# teensyShield1_1.net
KiCad netlist of a schematic drawn in EAGLE
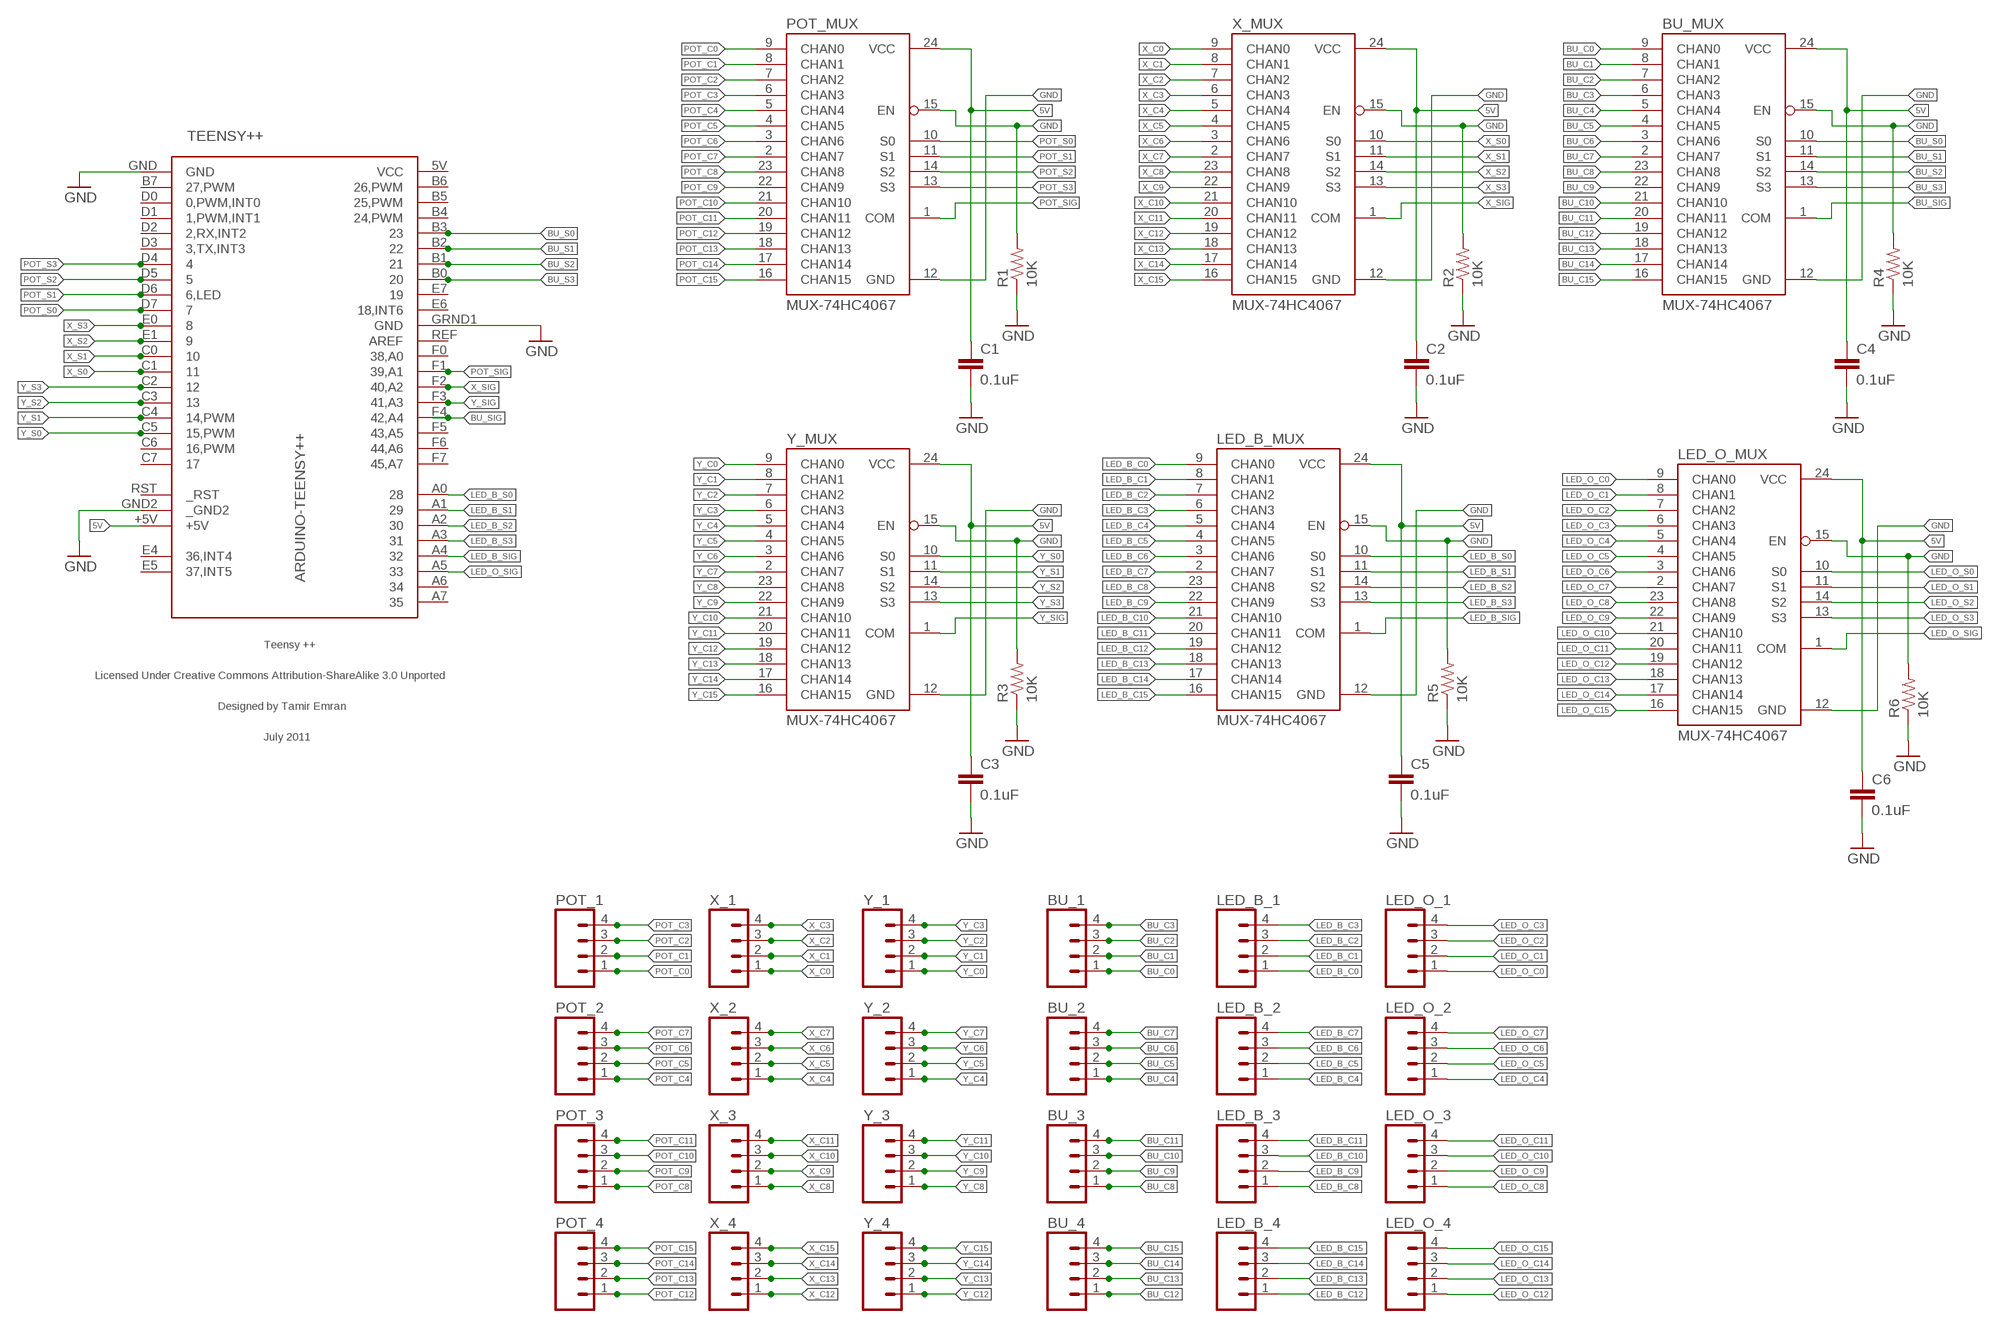
[diagram p0: schematic, sheet 1]

(export (version "E")
  (design (tool "Eeschema 10.0.6"))
  (components
    (comp (ref "BU_1")
      (value "M04NO_SILK_ALL_ROUND")
      (footprint "eagle-import:1X04_NO_SILK_ALL_ROUND")
      (libsource (lib "eagle-import") (part "M04NO_SILK_ALL_ROUND"))
    )
    (comp (ref "BU_2")
      (value "M04NO_SILK_ALL_ROUND")
      (footprint "eagle-import:1X04_NO_SILK_ALL_ROUND")
      (libsource (lib "eagle-import") (part "M04NO_SILK_ALL_ROUND"))
    )
    (comp (ref "BU_3")
      (value "M04NO_SILK_ALL_ROUND")
      (footprint "eagle-import:1X04_NO_SILK_ALL_ROUND")
      (libsource (lib "eagle-import") (part "M04NO_SILK_ALL_ROUND"))
    )
    (comp (ref "BU_4")
      (value "M04NO_SILK_ALL_ROUND")
      (footprint "eagle-import:1X04_NO_SILK_ALL_ROUND")
      (libsource (lib "eagle-import") (part "M04NO_SILK_ALL_ROUND"))
    )
    (comp (ref "BU_MUX")
      (value "MUX-74HC4067")
      (footprint "eagle-import:SSOP24")
      (libsource (lib "eagle-import") (part "MUX-74HC4067SMD"))
    )
    (comp (ref "C1")
      (value "0.1uF")
      (footprint "eagle-import:0603")
      (libsource (lib "eagle-import") (part "CAP0603"))
    )
    (comp (ref "C2")
      (value "0.1uF")
      (footprint "eagle-import:0603")
      (libsource (lib "eagle-import") (part "CAP0603"))
    )
    (comp (ref "C3")
      (value "0.1uF")
      (footprint "eagle-import:0603")
      (libsource (lib "eagle-import") (part "CAP0603"))
    )
    (comp (ref "C4")
      (value "0.1uF")
      (footprint "eagle-import:0603")
      (libsource (lib "eagle-import") (part "CAP0603"))
    )
    (comp (ref "C5")
      (value "0.1uF")
      (footprint "eagle-import:0603")
      (libsource (lib "eagle-import") (part "CAP0603"))
    )
    (comp (ref "C6")
      (value "0.1uF")
      (footprint "eagle-import:0603")
      (libsource (lib "eagle-import") (part "CAP0603"))
    )
    (comp (ref "LED_B_1")
      (value "M04NO_SILK_ALL_ROUND")
      (footprint "eagle-import:1X04_NO_SILK_ALL_ROUND")
      (libsource (lib "eagle-import") (part "M04NO_SILK_ALL_ROUND"))
    )
    (comp (ref "LED_B_2")
      (value "M04NO_SILK_ALL_ROUND")
      (footprint "eagle-import:1X04_NO_SILK_ALL_ROUND")
      (libsource (lib "eagle-import") (part "M04NO_SILK_ALL_ROUND"))
    )
    (comp (ref "LED_B_3")
      (value "M04NO_SILK_ALL_ROUND")
      (footprint "eagle-import:1X04_NO_SILK_ALL_ROUND")
      (libsource (lib "eagle-import") (part "M04NO_SILK_ALL_ROUND"))
    )
    (comp (ref "LED_B_4")
      (value "M04NO_SILK_ALL_ROUND")
      (footprint "eagle-import:1X04_NO_SILK_ALL_ROUND")
      (libsource (lib "eagle-import") (part "M04NO_SILK_ALL_ROUND"))
    )
    (comp (ref "LED_B_MUX")
      (value "MUX-74HC4067")
      (footprint "eagle-import:SSOP24")
      (libsource (lib "eagle-import") (part "MUX-74HC4067SMD"))
    )
    (comp (ref "LED_O_1")
      (value "M04NO_SILK_ALL_ROUND")
      (footprint "eagle-import:1X04_NO_SILK_ALL_ROUND")
      (libsource (lib "eagle-import") (part "M04NO_SILK_ALL_ROUND"))
    )
    (comp (ref "LED_O_2")
      (value "M04NO_SILK_ALL_ROUND")
      (footprint "eagle-import:1X04_NO_SILK_ALL_ROUND")
      (libsource (lib "eagle-import") (part "M04NO_SILK_ALL_ROUND"))
    )
    (comp (ref "LED_O_3")
      (value "M04NO_SILK_ALL_ROUND")
      (footprint "eagle-import:1X04_NO_SILK_ALL_ROUND")
      (libsource (lib "eagle-import") (part "M04NO_SILK_ALL_ROUND"))
    )
    (comp (ref "LED_O_4")
      (value "M04NO_SILK_ALL_ROUND")
      (footprint "eagle-import:1X04_NO_SILK_ALL_ROUND")
      (libsource (lib "eagle-import") (part "M04NO_SILK_ALL_ROUND"))
    )
    (comp (ref "LED_O_MUX")
      (value "MUX-74HC4067")
      (footprint "eagle-import:SSOP24")
      (libsource (lib "eagle-import") (part "MUX-74HC4067SMD"))
    )
    (comp (ref "POT_1")
      (value "M04NO_SILK_ALL_ROUND")
      (footprint "eagle-import:1X04_NO_SILK_ALL_ROUND")
      (libsource (lib "eagle-import") (part "M04NO_SILK_ALL_ROUND"))
    )
    (comp (ref "POT_2")
      (value "M04NO_SILK_ALL_ROUND")
      (footprint "eagle-import:1X04_NO_SILK_ALL_ROUND")
      (libsource (lib "eagle-import") (part "M04NO_SILK_ALL_ROUND"))
    )
    (comp (ref "POT_3")
      (value "M04NO_SILK_ALL_ROUND")
      (footprint "eagle-import:1X04_NO_SILK_ALL_ROUND")
      (libsource (lib "eagle-import") (part "M04NO_SILK_ALL_ROUND"))
    )
    (comp (ref "POT_4")
      (value "M04NO_SILK_ALL_ROUND")
      (footprint "eagle-import:1X04_NO_SILK_ALL_ROUND")
      (libsource (lib "eagle-import") (part "M04NO_SILK_ALL_ROUND"))
    )
    (comp (ref "POT_MUX")
      (value "MUX-74HC4067")
      (footprint "eagle-import:SSOP24")
      (libsource (lib "eagle-import") (part "MUX-74HC4067SMD"))
    )
    (comp (ref "R1")
      (value "10K")
      (footprint "eagle-import:0603")
      (libsource (lib "eagle-import") (part "RESISTOR0603"))
    )
    (comp (ref "R2")
      (value "10K")
      (footprint "eagle-import:0603")
      (libsource (lib "eagle-import") (part "RESISTOR0603"))
    )
    (comp (ref "R3")
      (value "10K")
      (footprint "eagle-import:0603")
      (libsource (lib "eagle-import") (part "RESISTOR0603"))
    )
    (comp (ref "R4")
      (value "10K")
      (footprint "eagle-import:0603")
      (libsource (lib "eagle-import") (part "RESISTOR0603"))
    )
    (comp (ref "R5")
      (value "10K")
      (footprint "eagle-import:0603")
      (libsource (lib "eagle-import") (part "RESISTOR0603"))
    )
    (comp (ref "R6")
      (value "10K")
      (footprint "eagle-import:0603")
      (libsource (lib "eagle-import") (part "RESISTOR0603"))
    )
    (comp (ref "TEENSY++")
      (value "ARDUINO-TEENSY++")
      (footprint "eagle-import:TEENSY++")
      (libsource (lib "eagle-import") (part "ARDUINO-TEENSY++"))
    )
    (comp (ref "X_1")
      (value "M04NO_SILK_ALL_ROUND")
      (footprint "eagle-import:1X04_NO_SILK_ALL_ROUND")
      (libsource (lib "eagle-import") (part "M04NO_SILK_ALL_ROUND"))
    )
    (comp (ref "X_2")
      (value "M04NO_SILK_ALL_ROUND")
      (footprint "eagle-import:1X04_NO_SILK_ALL_ROUND")
      (libsource (lib "eagle-import") (part "M04NO_SILK_ALL_ROUND"))
    )
    (comp (ref "X_3")
      (value "M04NO_SILK_ALL_ROUND")
      (footprint "eagle-import:1X04_NO_SILK_ALL_ROUND")
      (libsource (lib "eagle-import") (part "M04NO_SILK_ALL_ROUND"))
    )
    (comp (ref "X_4")
      (value "M04NO_SILK_ALL_ROUND")
      (footprint "eagle-import:1X04_NO_SILK_ALL_ROUND")
      (libsource (lib "eagle-import") (part "M04NO_SILK_ALL_ROUND"))
    )
    (comp (ref "X_MUX")
      (value "MUX-74HC4067")
      (footprint "eagle-import:SSOP24")
      (libsource (lib "eagle-import") (part "MUX-74HC4067SMD"))
    )
    (comp (ref "Y_1")
      (value "M04NO_SILK_ALL_ROUND")
      (footprint "eagle-import:1X04_NO_SILK_ALL_ROUND")
      (libsource (lib "eagle-import") (part "M04NO_SILK_ALL_ROUND"))
    )
    (comp (ref "Y_2")
      (value "M04NO_SILK_ALL_ROUND")
      (footprint "eagle-import:1X04_NO_SILK_ALL_ROUND")
      (libsource (lib "eagle-import") (part "M04NO_SILK_ALL_ROUND"))
    )
    (comp (ref "Y_3")
      (value "M04NO_SILK_ALL_ROUND")
      (footprint "eagle-import:1X04_NO_SILK_ALL_ROUND")
      (libsource (lib "eagle-import") (part "M04NO_SILK_ALL_ROUND"))
    )
    (comp (ref "Y_4")
      (value "M04NO_SILK_ALL_ROUND")
      (footprint "eagle-import:1X04_NO_SILK_ALL_ROUND")
      (libsource (lib "eagle-import") (part "M04NO_SILK_ALL_ROUND"))
    )
    (comp (ref "Y_MUX")
      (value "MUX-74HC4067")
      (footprint "eagle-import:SSOP24")
      (libsource (lib "eagle-import") (part "MUX-74HC4067SMD"))
    )
  )
  (nets
    (net (code "1") (name "/VCC") (class "Default")
      (node (ref "TEENSY++") (pin "5V") (pinfunction "VCC_5V") (pintype "power_in"))
    )
    (net (code "2") (name "5V") (class "Default")
      (node (ref "BU_MUX") (pin "24") (pinfunction "VCC_24") (pintype "bidirectional"))
      (node (ref "C1") (pin "1") (pinfunction "1_1") (pintype "passive"))
      (node (ref "C2") (pin "1") (pinfunction "1_1") (pintype "passive"))
      (node (ref "C3") (pin "1") (pinfunction "1_1") (pintype "passive"))
      (node (ref "C4") (pin "1") (pinfunction "1_1") (pintype "passive"))
      (node (ref "C5") (pin "1") (pinfunction "1_1") (pintype "passive"))
      (node (ref "C6") (pin "1") (pinfunction "1_1") (pintype "passive"))
      (node (ref "LED_B_MUX") (pin "24") (pinfunction "VCC_24") (pintype "bidirectional"))
      (node (ref "LED_O_MUX") (pin "24") (pinfunction "VCC_24") (pintype "bidirectional"))
      (node (ref "POT_MUX") (pin "24") (pinfunction "VCC_24") (pintype "bidirectional"))
      (node (ref "X_MUX") (pin "24") (pinfunction "VCC_24") (pintype "bidirectional"))
      (node (ref "Y_MUX") (pin "24") (pinfunction "VCC_24") (pintype "bidirectional"))
    )
    (net (code "3") (name "BU_C0") (class "Default")
      (node (ref "BU_1") (pin "1") (pinfunction "1_1") (pintype "passive"))
      (node (ref "BU_MUX") (pin "9") (pinfunction "CHAN0_9") (pintype "bidirectional"))
    )
    (net (code "4") (name "BU_C1") (class "Default")
      (node (ref "BU_1") (pin "2") (pinfunction "2_2") (pintype "passive"))
      (node (ref "BU_MUX") (pin "8") (pinfunction "CHAN1_8") (pintype "bidirectional"))
    )
    (net (code "5") (name "BU_C2") (class "Default")
      (node (ref "BU_1") (pin "3") (pinfunction "3_3") (pintype "passive"))
      (node (ref "BU_MUX") (pin "7") (pinfunction "CHAN2_7") (pintype "bidirectional"))
    )
    (net (code "6") (name "BU_C3") (class "Default")
      (node (ref "BU_1") (pin "4") (pinfunction "4_4") (pintype "passive"))
      (node (ref "BU_MUX") (pin "6") (pinfunction "CHAN3_6") (pintype "bidirectional"))
    )
    (net (code "7") (name "BU_C4") (class "Default")
      (node (ref "BU_2") (pin "1") (pinfunction "1_1") (pintype "passive"))
      (node (ref "BU_MUX") (pin "5") (pinfunction "CHAN4_5") (pintype "bidirectional"))
    )
    (net (code "8") (name "BU_C5") (class "Default")
      (node (ref "BU_2") (pin "2") (pinfunction "2_2") (pintype "passive"))
      (node (ref "BU_MUX") (pin "4") (pinfunction "CHAN5_4") (pintype "bidirectional"))
    )
    (net (code "9") (name "BU_C6") (class "Default")
      (node (ref "BU_2") (pin "3") (pinfunction "3_3") (pintype "passive"))
      (node (ref "BU_MUX") (pin "3") (pinfunction "CHAN6_3") (pintype "bidirectional"))
    )
    (net (code "10") (name "BU_C7") (class "Default")
      (node (ref "BU_2") (pin "4") (pinfunction "4_4") (pintype "passive"))
      (node (ref "BU_MUX") (pin "2") (pinfunction "CHAN7_2") (pintype "bidirectional"))
    )
    (net (code "11") (name "BU_C8") (class "Default")
      (node (ref "BU_3") (pin "1") (pinfunction "1_1") (pintype "passive"))
      (node (ref "BU_MUX") (pin "23") (pinfunction "CHAN8_23") (pintype "bidirectional"))
    )
    (net (code "12") (name "BU_C9") (class "Default")
      (node (ref "BU_3") (pin "2") (pinfunction "2_2") (pintype "passive"))
      (node (ref "BU_MUX") (pin "22") (pinfunction "CHAN9_22") (pintype "bidirectional"))
    )
    (net (code "13") (name "BU_C10") (class "Default")
      (node (ref "BU_3") (pin "3") (pinfunction "3_3") (pintype "passive"))
      (node (ref "BU_MUX") (pin "21") (pinfunction "CHAN10_21") (pintype "bidirectional"))
    )
    (net (code "14") (name "BU_C11") (class "Default")
      (node (ref "BU_3") (pin "4") (pinfunction "4_4") (pintype "passive"))
      (node (ref "BU_MUX") (pin "20") (pinfunction "CHAN11_20") (pintype "bidirectional"))
    )
    (net (code "15") (name "BU_C12") (class "Default")
      (node (ref "BU_4") (pin "1") (pinfunction "1_1") (pintype "passive"))
      (node (ref "BU_MUX") (pin "19") (pinfunction "CHAN12_19") (pintype "bidirectional"))
    )
    (net (code "16") (name "BU_C13") (class "Default")
      (node (ref "BU_4") (pin "2") (pinfunction "2_2") (pintype "passive"))
      (node (ref "BU_MUX") (pin "18") (pinfunction "CHAN13_18") (pintype "bidirectional"))
    )
    (net (code "17") (name "BU_C14") (class "Default")
      (node (ref "BU_4") (pin "3") (pinfunction "3_3") (pintype "passive"))
      (node (ref "BU_MUX") (pin "17") (pinfunction "CHAN14_17") (pintype "bidirectional"))
    )
    (net (code "18") (name "BU_C15") (class "Default")
      (node (ref "BU_4") (pin "4") (pinfunction "4_4") (pintype "passive"))
      (node (ref "BU_MUX") (pin "16") (pinfunction "CHAN15_16") (pintype "bidirectional"))
    )
    (net (code "19") (name "BU_S0") (class "Default")
      (node (ref "BU_MUX") (pin "10") (pinfunction "S0_10") (pintype "input"))
      (node (ref "TEENSY++") (pin "B3") (pinfunction "23_B3") (pintype "bidirectional"))
    )
    (net (code "20") (name "BU_S1") (class "Default")
      (node (ref "BU_MUX") (pin "11") (pinfunction "S1_11") (pintype "input"))
      (node (ref "TEENSY++") (pin "B2") (pinfunction "22_B2") (pintype "bidirectional"))
    )
    (net (code "21") (name "BU_S2") (class "Default")
      (node (ref "BU_MUX") (pin "14") (pinfunction "S2_14") (pintype "input"))
      (node (ref "TEENSY++") (pin "B1") (pinfunction "21_B1") (pintype "bidirectional"))
    )
    (net (code "22") (name "BU_S3") (class "Default")
      (node (ref "BU_MUX") (pin "13") (pinfunction "S3_13") (pintype "input"))
      (node (ref "TEENSY++") (pin "B0") (pinfunction "20_B0") (pintype "bidirectional"))
    )
    (net (code "23") (name "BU_SIG") (class "Default")
      (node (ref "BU_MUX") (pin "1") (pinfunction "COM_1") (pintype "bidirectional"))
      (node (ref "TEENSY++") (pin "F4") (pinfunction "42,A4_F4") (pintype "bidirectional"))
    )
    (net (code "24") (name "GND") (class "Default")
      (node (ref "BU_MUX") (pin "12") (pinfunction "GND_12") (pintype "bidirectional"))
      (node (ref "BU_MUX") (pin "15") (pinfunction "EN_15") (pintype "input"))
      (node (ref "C1") (pin "2") (pinfunction "2_2") (pintype "passive"))
      (node (ref "C2") (pin "2") (pinfunction "2_2") (pintype "passive"))
      (node (ref "C3") (pin "2") (pinfunction "2_2") (pintype "passive"))
      (node (ref "C4") (pin "2") (pinfunction "2_2") (pintype "passive"))
      (node (ref "C5") (pin "2") (pinfunction "2_2") (pintype "passive"))
      (node (ref "C6") (pin "2") (pinfunction "2_2") (pintype "passive"))
      (node (ref "LED_B_MUX") (pin "12") (pinfunction "GND_12") (pintype "bidirectional"))
      (node (ref "LED_B_MUX") (pin "15") (pinfunction "EN_15") (pintype "input"))
      (node (ref "LED_O_MUX") (pin "12") (pinfunction "GND_12") (pintype "bidirectional"))
      (node (ref "LED_O_MUX") (pin "15") (pinfunction "EN_15") (pintype "input"))
      (node (ref "POT_MUX") (pin "12") (pinfunction "GND_12") (pintype "bidirectional"))
      (node (ref "POT_MUX") (pin "15") (pinfunction "EN_15") (pintype "input"))
      (node (ref "R1") (pin "1") (pinfunction "1_1") (pintype "passive"))
      (node (ref "R1") (pin "2") (pinfunction "2_2") (pintype "passive"))
      (node (ref "R2") (pin "1") (pinfunction "1_1") (pintype "passive"))
      (node (ref "R2") (pin "2") (pinfunction "2_2") (pintype "passive"))
      (node (ref "R3") (pin "1") (pinfunction "1_1") (pintype "passive"))
      (node (ref "R3") (pin "2") (pinfunction "2_2") (pintype "passive"))
      (node (ref "R4") (pin "1") (pinfunction "1_1") (pintype "passive"))
      (node (ref "R4") (pin "2") (pinfunction "2_2") (pintype "passive"))
      (node (ref "R5") (pin "1") (pinfunction "1_1") (pintype "passive"))
      (node (ref "R5") (pin "2") (pinfunction "2_2") (pintype "passive"))
      (node (ref "R6") (pin "1") (pinfunction "1_1") (pintype "passive"))
      (node (ref "R6") (pin "2") (pinfunction "2_2") (pintype "passive"))
      (node (ref "TEENSY++") (pin "GND") (pinfunction "GND_GND") (pintype "power_in"))
      (node (ref "TEENSY++") (pin "GND2") (pinfunction "_GND2_GND2") (pintype "power_in"))
      (node (ref "TEENSY++") (pin "GRND1") (pinfunction "GND_GRND1") (pintype "power_in"))
      (node (ref "X_MUX") (pin "12") (pinfunction "GND_12") (pintype "bidirectional"))
      (node (ref "X_MUX") (pin "15") (pinfunction "EN_15") (pintype "input"))
      (node (ref "Y_MUX") (pin "12") (pinfunction "GND_12") (pintype "bidirectional"))
      (node (ref "Y_MUX") (pin "15") (pinfunction "EN_15") (pintype "input"))
    )
    (net (code "25") (name "LED_B_C0") (class "Default")
      (node (ref "LED_B_1") (pin "1") (pinfunction "1_1") (pintype "passive"))
      (node (ref "LED_B_MUX") (pin "9") (pinfunction "CHAN0_9") (pintype "bidirectional"))
    )
    (net (code "26") (name "LED_B_C1") (class "Default")
      (node (ref "LED_B_1") (pin "2") (pinfunction "2_2") (pintype "passive"))
      (node (ref "LED_B_MUX") (pin "8") (pinfunction "CHAN1_8") (pintype "bidirectional"))
    )
    (net (code "27") (name "LED_B_C2") (class "Default")
      (node (ref "LED_B_1") (pin "3") (pinfunction "3_3") (pintype "passive"))
      (node (ref "LED_B_MUX") (pin "7") (pinfunction "CHAN2_7") (pintype "bidirectional"))
    )
    (net (code "28") (name "LED_B_C3") (class "Default")
      (node (ref "LED_B_1") (pin "4") (pinfunction "4_4") (pintype "passive"))
      (node (ref "LED_B_MUX") (pin "6") (pinfunction "CHAN3_6") (pintype "bidirectional"))
    )
    (net (code "29") (name "LED_B_C4") (class "Default")
      (node (ref "LED_B_2") (pin "1") (pinfunction "1_1") (pintype "passive"))
      (node (ref "LED_B_MUX") (pin "5") (pinfunction "CHAN4_5") (pintype "bidirectional"))
    )
    (net (code "30") (name "LED_B_C5") (class "Default")
      (node (ref "LED_B_2") (pin "2") (pinfunction "2_2") (pintype "passive"))
      (node (ref "LED_B_MUX") (pin "4") (pinfunction "CHAN5_4") (pintype "bidirectional"))
    )
    (net (code "31") (name "LED_B_C6") (class "Default")
      (node (ref "LED_B_2") (pin "3") (pinfunction "3_3") (pintype "passive"))
      (node (ref "LED_B_MUX") (pin "3") (pinfunction "CHAN6_3") (pintype "bidirectional"))
    )
    (net (code "32") (name "LED_B_C7") (class "Default")
      (node (ref "LED_B_2") (pin "4") (pinfunction "4_4") (pintype "passive"))
      (node (ref "LED_B_MUX") (pin "2") (pinfunction "CHAN7_2") (pintype "bidirectional"))
    )
    (net (code "33") (name "LED_B_C8") (class "Default")
      (node (ref "LED_B_3") (pin "1") (pinfunction "1_1") (pintype "passive"))
      (node (ref "LED_B_MUX") (pin "23") (pinfunction "CHAN8_23") (pintype "bidirectional"))
    )
    (net (code "34") (name "LED_B_C9") (class "Default")
      (node (ref "LED_B_3") (pin "2") (pinfunction "2_2") (pintype "passive"))
      (node (ref "LED_B_MUX") (pin "22") (pinfunction "CHAN9_22") (pintype "bidirectional"))
    )
    (net (code "35") (name "LED_B_C10") (class "Default")
      (node (ref "LED_B_3") (pin "3") (pinfunction "3_3") (pintype "passive"))
      (node (ref "LED_B_MUX") (pin "21") (pinfunction "CHAN10_21") (pintype "bidirectional"))
    )
    (net (code "36") (name "LED_B_C11") (class "Default")
      (node (ref "LED_B_3") (pin "4") (pinfunction "4_4") (pintype "passive"))
      (node (ref "LED_B_MUX") (pin "20") (pinfunction "CHAN11_20") (pintype "bidirectional"))
    )
    (net (code "37") (name "LED_B_C12") (class "Default")
      (node (ref "LED_B_4") (pin "1") (pinfunction "1_1") (pintype "passive"))
      (node (ref "LED_B_MUX") (pin "19") (pinfunction "CHAN12_19") (pintype "bidirectional"))
    )
    (net (code "38") (name "LED_B_C13") (class "Default")
      (node (ref "LED_B_4") (pin "2") (pinfunction "2_2") (pintype "passive"))
      (node (ref "LED_B_MUX") (pin "18") (pinfunction "CHAN13_18") (pintype "bidirectional"))
    )
    (net (code "39") (name "LED_B_C14") (class "Default")
      (node (ref "LED_B_4") (pin "3") (pinfunction "3_3") (pintype "passive"))
      (node (ref "LED_B_MUX") (pin "17") (pinfunction "CHAN14_17") (pintype "bidirectional"))
    )
    (net (code "40") (name "LED_B_C15") (class "Default")
      (node (ref "LED_B_4") (pin "4") (pinfunction "4_4") (pintype "passive"))
      (node (ref "LED_B_MUX") (pin "16") (pinfunction "CHAN15_16") (pintype "bidirectional"))
    )
    (net (code "41") (name "LED_B_S0") (class "Default")
      (node (ref "LED_B_MUX") (pin "10") (pinfunction "S0_10") (pintype "input"))
      (node (ref "TEENSY++") (pin "A0") (pinfunction "28_A0") (pintype "bidirectional"))
    )
    (net (code "42") (name "LED_B_S1") (class "Default")
      (node (ref "LED_B_MUX") (pin "11") (pinfunction "S1_11") (pintype "input"))
      (node (ref "TEENSY++") (pin "A1") (pinfunction "29_A1") (pintype "bidirectional"))
    )
    (net (code "43") (name "LED_B_S2") (class "Default")
      (node (ref "LED_B_MUX") (pin "14") (pinfunction "S2_14") (pintype "input"))
      (node (ref "TEENSY++") (pin "A2") (pinfunction "30_A2") (pintype "bidirectional"))
    )
    (net (code "44") (name "LED_B_S3") (class "Default")
      (node (ref "LED_B_MUX") (pin "13") (pinfunction "S3_13") (pintype "input"))
      (node (ref "TEENSY++") (pin "A3") (pinfunction "31_A3") (pintype "bidirectional"))
    )
    (net (code "45") (name "LED_B_SIG") (class "Default")
      (node (ref "LED_B_MUX") (pin "1") (pinfunction "COM_1") (pintype "bidirectional"))
    )
    (net (code "46") (name "LED_O_C0") (class "Default")
      (node (ref "LED_O_1") (pin "1") (pinfunction "1_1") (pintype "passive"))
      (node (ref "LED_O_MUX") (pin "9") (pinfunction "CHAN0_9") (pintype "bidirectional"))
    )
    (net (code "47") (name "LED_O_C1") (class "Default")
      (node (ref "LED_O_1") (pin "2") (pinfunction "2_2") (pintype "passive"))
      (node (ref "LED_O_MUX") (pin "8") (pinfunction "CHAN1_8") (pintype "bidirectional"))
    )
    (net (code "48") (name "LED_O_C2") (class "Default")
      (node (ref "LED_O_1") (pin "3") (pinfunction "3_3") (pintype "passive"))
      (node (ref "LED_O_MUX") (pin "7") (pinfunction "CHAN2_7") (pintype "bidirectional"))
    )
    (net (code "49") (name "LED_O_C3") (class "Default")
      (node (ref "LED_O_1") (pin "4") (pinfunction "4_4") (pintype "passive"))
      (node (ref "LED_O_MUX") (pin "6") (pinfunction "CHAN3_6") (pintype "bidirectional"))
    )
    (net (code "50") (name "LED_O_C4") (class "Default")
      (node (ref "LED_O_2") (pin "1") (pinfunction "1_1") (pintype "passive"))
      (node (ref "LED_O_MUX") (pin "5") (pinfunction "CHAN4_5") (pintype "bidirectional"))
    )
    (net (code "51") (name "LED_O_C5") (class "Default")
      (node (ref "LED_O_2") (pin "2") (pinfunction "2_2") (pintype "passive"))
      (node (ref "LED_O_MUX") (pin "4") (pinfunction "CHAN5_4") (pintype "bidirectional"))
    )
    (net (code "52") (name "LED_O_C6") (class "Default")
      (node (ref "LED_O_2") (pin "3") (pinfunction "3_3") (pintype "passive"))
      (node (ref "LED_O_MUX") (pin "3") (pinfunction "CHAN6_3") (pintype "bidirectional"))
    )
    (net (code "53") (name "LED_O_C7") (class "Default")
      (node (ref "LED_O_2") (pin "4") (pinfunction "4_4") (pintype "passive"))
      (node (ref "LED_O_MUX") (pin "2") (pinfunction "CHAN7_2") (pintype "bidirectional"))
    )
    (net (code "54") (name "LED_O_C8") (class "Default")
      (node (ref "LED_O_3") (pin "1") (pinfunction "1_1") (pintype "passive"))
      (node (ref "LED_O_MUX") (pin "23") (pinfunction "CHAN8_23") (pintype "bidirectional"))
    )
    (net (code "55") (name "LED_O_C9") (class "Default")
      (node (ref "LED_O_3") (pin "2") (pinfunction "2_2") (pintype "passive"))
      (node (ref "LED_O_MUX") (pin "22") (pinfunction "CHAN9_22") (pintype "bidirectional"))
    )
    (net (code "56") (name "LED_O_C10") (class "Default")
      (node (ref "LED_O_3") (pin "3") (pinfunction "3_3") (pintype "passive"))
      (node (ref "LED_O_MUX") (pin "21") (pinfunction "CHAN10_21") (pintype "bidirectional"))
    )
    (net (code "57") (name "LED_O_C11") (class "Default")
      (node (ref "LED_O_3") (pin "4") (pinfunction "4_4") (pintype "passive"))
      (node (ref "LED_O_MUX") (pin "20") (pinfunction "CHAN11_20") (pintype "bidirectional"))
    )
    (net (code "58") (name "LED_O_C12") (class "Default")
      (node (ref "LED_O_4") (pin "1") (pinfunction "1_1") (pintype "passive"))
      (node (ref "LED_O_MUX") (pin "19") (pinfunction "CHAN12_19") (pintype "bidirectional"))
    )
    (net (code "59") (name "LED_O_C13") (class "Default")
      (node (ref "LED_O_4") (pin "2") (pinfunction "2_2") (pintype "passive"))
      (node (ref "LED_O_MUX") (pin "18") (pinfunction "CHAN13_18") (pintype "bidirectional"))
    )
    (net (code "60") (name "LED_O_C14") (class "Default")
      (node (ref "LED_O_4") (pin "3") (pinfunction "3_3") (pintype "passive"))
      (node (ref "LED_O_MUX") (pin "17") (pinfunction "CHAN14_17") (pintype "bidirectional"))
    )
    (net (code "61") (name "LED_O_C15") (class "Default")
      (node (ref "LED_O_4") (pin "4") (pinfunction "4_4") (pintype "passive"))
      (node (ref "LED_O_MUX") (pin "16") (pinfunction "CHAN15_16") (pintype "bidirectional"))
    )
    (net (code "62") (name "LED_O_S0") (class "Default")
      (node (ref "LED_O_MUX") (pin "10") (pinfunction "S0_10") (pintype "input"))
    )
    (net (code "63") (name "LED_O_S1") (class "Default")
      (node (ref "LED_O_MUX") (pin "11") (pinfunction "S1_11") (pintype "input"))
    )
    (net (code "64") (name "LED_O_S2") (class "Default")
      (node (ref "LED_O_MUX") (pin "14") (pinfunction "S2_14") (pintype "input"))
    )
    (net (code "65") (name "LED_O_S3") (class "Default")
      (node (ref "LED_O_MUX") (pin "13") (pinfunction "S3_13") (pintype "input"))
    )
    (net (code "66") (name "LED_O_SIG") (class "Default")
      (node (ref "LED_O_MUX") (pin "1") (pinfunction "COM_1") (pintype "bidirectional"))
    )
    (net (code "67") (name "POT_C0") (class "Default")
      (node (ref "POT_1") (pin "1") (pinfunction "1_1") (pintype "passive"))
      (node (ref "POT_MUX") (pin "9") (pinfunction "CHAN0_9") (pintype "bidirectional"))
    )
    (net (code "68") (name "POT_C1") (class "Default")
      (node (ref "POT_1") (pin "2") (pinfunction "2_2") (pintype "passive"))
      (node (ref "POT_MUX") (pin "8") (pinfunction "CHAN1_8") (pintype "bidirectional"))
    )
    (net (code "69") (name "POT_C2") (class "Default")
      (node (ref "POT_1") (pin "3") (pinfunction "3_3") (pintype "passive"))
      (node (ref "POT_MUX") (pin "7") (pinfunction "CHAN2_7") (pintype "bidirectional"))
    )
    (net (code "70") (name "POT_C3") (class "Default")
      (node (ref "POT_1") (pin "4") (pinfunction "4_4") (pintype "passive"))
      (node (ref "POT_MUX") (pin "6") (pinfunction "CHAN3_6") (pintype "bidirectional"))
    )
    (net (code "71") (name "POT_C4") (class "Default")
      (node (ref "POT_2") (pin "1") (pinfunction "1_1") (pintype "passive"))
      (node (ref "POT_MUX") (pin "5") (pinfunction "CHAN4_5") (pintype "bidirectional"))
    )
    (net (code "72") (name "POT_C5") (class "Default")
      (node (ref "POT_2") (pin "2") (pinfunction "2_2") (pintype "passive"))
      (node (ref "POT_MUX") (pin "4") (pinfunction "CHAN5_4") (pintype "bidirectional"))
    )
    (net (code "73") (name "POT_C6") (class "Default")
      (node (ref "POT_2") (pin "3") (pinfunction "3_3") (pintype "passive"))
      (node (ref "POT_MUX") (pin "3") (pinfunction "CHAN6_3") (pintype "bidirectional"))
    )
    (net (code "74") (name "POT_C7") (class "Default")
      (node (ref "POT_2") (pin "4") (pinfunction "4_4") (pintype "passive"))
      (node (ref "POT_MUX") (pin "2") (pinfunction "CHAN7_2") (pintype "bidirectional"))
    )
    (net (code "75") (name "POT_C8") (class "Default")
      (node (ref "POT_3") (pin "1") (pinfunction "1_1") (pintype "passive"))
      (node (ref "POT_MUX") (pin "23") (pinfunction "CHAN8_23") (pintype "bidirectional"))
    )
    (net (code "76") (name "POT_C9") (class "Default")
      (node (ref "POT_3") (pin "2") (pinfunction "2_2") (pintype "passive"))
      (node (ref "POT_MUX") (pin "22") (pinfunction "CHAN9_22") (pintype "bidirectional"))
    )
    (net (code "77") (name "POT_C10") (class "Default")
      (node (ref "POT_3") (pin "3") (pinfunction "3_3") (pintype "passive"))
      (node (ref "POT_MUX") (pin "21") (pinfunction "CHAN10_21") (pintype "bidirectional"))
    )
    (net (code "78") (name "POT_C11") (class "Default")
      (node (ref "POT_3") (pin "4") (pinfunction "4_4") (pintype "passive"))
      (node (ref "POT_MUX") (pin "20") (pinfunction "CHAN11_20") (pintype "bidirectional"))
    )
    (net (code "79") (name "POT_C12") (class "Default")
      (node (ref "POT_4") (pin "1") (pinfunction "1_1") (pintype "passive"))
      (node (ref "POT_MUX") (pin "19") (pinfunction "CHAN12_19") (pintype "bidirectional"))
    )
    (net (code "80") (name "POT_C13") (class "Default")
      (node (ref "POT_4") (pin "2") (pinfunction "2_2") (pintype "passive"))
      (node (ref "POT_MUX") (pin "18") (pinfunction "CHAN13_18") (pintype "bidirectional"))
    )
    (net (code "81") (name "POT_C14") (class "Default")
      (node (ref "POT_4") (pin "3") (pinfunction "3_3") (pintype "passive"))
      (node (ref "POT_MUX") (pin "17") (pinfunction "CHAN14_17") (pintype "bidirectional"))
    )
    (net (code "82") (name "POT_C15") (class "Default")
      (node (ref "POT_4") (pin "4") (pinfunction "4_4") (pintype "passive"))
      (node (ref "POT_MUX") (pin "16") (pinfunction "CHAN15_16") (pintype "bidirectional"))
    )
    (net (code "83") (name "POT_S0") (class "Default")
      (node (ref "POT_MUX") (pin "10") (pinfunction "S0_10") (pintype "input"))
      (node (ref "TEENSY++") (pin "D7") (pinfunction "7_D7") (pintype "bidirectional"))
    )
    (net (code "84") (name "POT_S1") (class "Default")
      (node (ref "POT_MUX") (pin "11") (pinfunction "S1_11") (pintype "input"))
      (node (ref "TEENSY++") (pin "D6") (pinfunction "6,LED_D6") (pintype "bidirectional"))
    )
    (net (code "85") (name "POT_S2") (class "Default")
      (node (ref "POT_MUX") (pin "14") (pinfunction "S2_14") (pintype "input"))
      (node (ref "TEENSY++") (pin "D5") (pinfunction "5_D5") (pintype "bidirectional"))
    )
    (net (code "86") (name "POT_S3") (class "Default")
      (node (ref "POT_MUX") (pin "13") (pinfunction "S3_13") (pintype "input"))
      (node (ref "TEENSY++") (pin "D4") (pinfunction "4_D4") (pintype "bidirectional"))
    )
    (net (code "87") (name "POT_SIG") (class "Default")
      (node (ref "POT_MUX") (pin "1") (pinfunction "COM_1") (pintype "bidirectional"))
    )
    (net (code "88") (name "X_C0") (class "Default")
      (node (ref "X_1") (pin "1") (pinfunction "1_1") (pintype "passive"))
      (node (ref "X_MUX") (pin "9") (pinfunction "CHAN0_9") (pintype "bidirectional"))
    )
    (net (code "89") (name "X_C1") (class "Default")
      (node (ref "X_1") (pin "2") (pinfunction "2_2") (pintype "passive"))
      (node (ref "X_MUX") (pin "8") (pinfunction "CHAN1_8") (pintype "bidirectional"))
    )
    (net (code "90") (name "X_C2") (class "Default")
      (node (ref "X_1") (pin "3") (pinfunction "3_3") (pintype "passive"))
      (node (ref "X_MUX") (pin "7") (pinfunction "CHAN2_7") (pintype "bidirectional"))
    )
    (net (code "91") (name "X_C3") (class "Default")
      (node (ref "X_1") (pin "4") (pinfunction "4_4") (pintype "passive"))
      (node (ref "X_MUX") (pin "6") (pinfunction "CHAN3_6") (pintype "bidirectional"))
    )
    (net (code "92") (name "X_C4") (class "Default")
      (node (ref "X_2") (pin "1") (pinfunction "1_1") (pintype "passive"))
      (node (ref "X_MUX") (pin "5") (pinfunction "CHAN4_5") (pintype "bidirectional"))
    )
    (net (code "93") (name "X_C5") (class "Default")
      (node (ref "X_2") (pin "2") (pinfunction "2_2") (pintype "passive"))
      (node (ref "X_MUX") (pin "4") (pinfunction "CHAN5_4") (pintype "bidirectional"))
    )
    (net (code "94") (name "X_C6") (class "Default")
      (node (ref "X_2") (pin "3") (pinfunction "3_3") (pintype "passive"))
      (node (ref "X_MUX") (pin "3") (pinfunction "CHAN6_3") (pintype "bidirectional"))
    )
    (net (code "95") (name "X_C7") (class "Default")
      (node (ref "X_2") (pin "4") (pinfunction "4_4") (pintype "passive"))
      (node (ref "X_MUX") (pin "2") (pinfunction "CHAN7_2") (pintype "bidirectional"))
    )
    (net (code "96") (name "X_C8") (class "Default")
      (node (ref "X_3") (pin "1") (pinfunction "1_1") (pintype "passive"))
      (node (ref "X_MUX") (pin "23") (pinfunction "CHAN8_23") (pintype "bidirectional"))
    )
    (net (code "97") (name "X_C9") (class "Default")
      (node (ref "X_3") (pin "2") (pinfunction "2_2") (pintype "passive"))
      (node (ref "X_MUX") (pin "22") (pinfunction "CHAN9_22") (pintype "bidirectional"))
    )
    (net (code "98") (name "X_C10") (class "Default")
      (node (ref "X_3") (pin "3") (pinfunction "3_3") (pintype "passive"))
      (node (ref "X_MUX") (pin "21") (pinfunction "CHAN10_21") (pintype "bidirectional"))
    )
    (net (code "99") (name "X_C11") (class "Default")
      (node (ref "X_3") (pin "4") (pinfunction "4_4") (pintype "passive"))
      (node (ref "X_MUX") (pin "20") (pinfunction "CHAN11_20") (pintype "bidirectional"))
    )
    (net (code "100") (name "X_C12") (class "Default")
      (node (ref "X_4") (pin "1") (pinfunction "1_1") (pintype "passive"))
      (node (ref "X_MUX") (pin "19") (pinfunction "CHAN12_19") (pintype "bidirectional"))
    )
    (net (code "101") (name "X_C13") (class "Default")
      (node (ref "X_4") (pin "2") (pinfunction "2_2") (pintype "passive"))
      (node (ref "X_MUX") (pin "18") (pinfunction "CHAN13_18") (pintype "bidirectional"))
    )
    (net (code "102") (name "X_C14") (class "Default")
      (node (ref "X_4") (pin "3") (pinfunction "3_3") (pintype "passive"))
      (node (ref "X_MUX") (pin "17") (pinfunction "CHAN14_17") (pintype "bidirectional"))
    )
    (net (code "103") (name "X_C15") (class "Default")
      (node (ref "X_4") (pin "4") (pinfunction "4_4") (pintype "passive"))
      (node (ref "X_MUX") (pin "16") (pinfunction "CHAN15_16") (pintype "bidirectional"))
    )
    (net (code "104") (name "X_S0") (class "Default")
      (node (ref "TEENSY++") (pin "C1") (pinfunction "11_C1") (pintype "bidirectional"))
      (node (ref "X_MUX") (pin "10") (pinfunction "S0_10") (pintype "input"))
    )
    (net (code "105") (name "X_S1") (class "Default")
      (node (ref "TEENSY++") (pin "C0") (pinfunction "10_C0") (pintype "bidirectional"))
      (node (ref "X_MUX") (pin "11") (pinfunction "S1_11") (pintype "input"))
    )
    (net (code "106") (name "X_S2") (class "Default")
      (node (ref "TEENSY++") (pin "E1") (pinfunction "9_E1") (pintype "bidirectional"))
      (node (ref "X_MUX") (pin "14") (pinfunction "S2_14") (pintype "input"))
    )
    (net (code "107") (name "X_S3") (class "Default")
      (node (ref "TEENSY++") (pin "E0") (pinfunction "8_E0") (pintype "bidirectional"))
      (node (ref "X_MUX") (pin "13") (pinfunction "S3_13") (pintype "input"))
    )
    (net (code "108") (name "X_SIG") (class "Default")
      (node (ref "X_MUX") (pin "1") (pinfunction "COM_1") (pintype "bidirectional"))
    )
    (net (code "109") (name "Y_C0") (class "Default")
      (node (ref "Y_1") (pin "1") (pinfunction "1_1") (pintype "passive"))
      (node (ref "Y_MUX") (pin "9") (pinfunction "CHAN0_9") (pintype "bidirectional"))
    )
    (net (code "110") (name "Y_C1") (class "Default")
      (node (ref "Y_1") (pin "2") (pinfunction "2_2") (pintype "passive"))
      (node (ref "Y_MUX") (pin "8") (pinfunction "CHAN1_8") (pintype "bidirectional"))
    )
    (net (code "111") (name "Y_C2") (class "Default")
      (node (ref "Y_1") (pin "3") (pinfunction "3_3") (pintype "passive"))
      (node (ref "Y_MUX") (pin "7") (pinfunction "CHAN2_7") (pintype "bidirectional"))
    )
    (net (code "112") (name "Y_C3") (class "Default")
      (node (ref "Y_1") (pin "4") (pinfunction "4_4") (pintype "passive"))
      (node (ref "Y_MUX") (pin "6") (pinfunction "CHAN3_6") (pintype "bidirectional"))
    )
    (net (code "113") (name "Y_C4") (class "Default")
      (node (ref "Y_2") (pin "1") (pinfunction "1_1") (pintype "passive"))
      (node (ref "Y_MUX") (pin "5") (pinfunction "CHAN4_5") (pintype "bidirectional"))
    )
    (net (code "114") (name "Y_C5") (class "Default")
      (node (ref "Y_2") (pin "2") (pinfunction "2_2") (pintype "passive"))
      (node (ref "Y_MUX") (pin "4") (pinfunction "CHAN5_4") (pintype "bidirectional"))
    )
    (net (code "115") (name "Y_C6") (class "Default")
      (node (ref "Y_2") (pin "3") (pinfunction "3_3") (pintype "passive"))
      (node (ref "Y_MUX") (pin "3") (pinfunction "CHAN6_3") (pintype "bidirectional"))
    )
    (net (code "116") (name "Y_C7") (class "Default")
      (node (ref "Y_2") (pin "4") (pinfunction "4_4") (pintype "passive"))
      (node (ref "Y_MUX") (pin "2") (pinfunction "CHAN7_2") (pintype "bidirectional"))
    )
    (net (code "117") (name "Y_C8") (class "Default")
      (node (ref "Y_3") (pin "1") (pinfunction "1_1") (pintype "passive"))
      (node (ref "Y_MUX") (pin "23") (pinfunction "CHAN8_23") (pintype "bidirectional"))
    )
    (net (code "118") (name "Y_C9") (class "Default")
      (node (ref "Y_3") (pin "2") (pinfunction "2_2") (pintype "passive"))
      (node (ref "Y_MUX") (pin "22") (pinfunction "CHAN9_22") (pintype "bidirectional"))
    )
    (net (code "119") (name "Y_C10") (class "Default")
      (node (ref "Y_3") (pin "3") (pinfunction "3_3") (pintype "passive"))
      (node (ref "Y_MUX") (pin "21") (pinfunction "CHAN10_21") (pintype "bidirectional"))
    )
    (net (code "120") (name "Y_C11") (class "Default")
      (node (ref "Y_3") (pin "4") (pinfunction "4_4") (pintype "passive"))
      (node (ref "Y_MUX") (pin "20") (pinfunction "CHAN11_20") (pintype "bidirectional"))
    )
    (net (code "121") (name "Y_C12") (class "Default")
      (node (ref "Y_4") (pin "1") (pinfunction "1_1") (pintype "passive"))
      (node (ref "Y_MUX") (pin "19") (pinfunction "CHAN12_19") (pintype "bidirectional"))
    )
    (net (code "122") (name "Y_C13") (class "Default")
      (node (ref "Y_4") (pin "2") (pinfunction "2_2") (pintype "passive"))
      (node (ref "Y_MUX") (pin "18") (pinfunction "CHAN13_18") (pintype "bidirectional"))
    )
    (net (code "123") (name "Y_C14") (class "Default")
      (node (ref "Y_4") (pin "3") (pinfunction "3_3") (pintype "passive"))
      (node (ref "Y_MUX") (pin "17") (pinfunction "CHAN14_17") (pintype "bidirectional"))
    )
    (net (code "124") (name "Y_C15") (class "Default")
      (node (ref "Y_4") (pin "4") (pinfunction "4_4") (pintype "passive"))
      (node (ref "Y_MUX") (pin "16") (pinfunction "CHAN15_16") (pintype "bidirectional"))
    )
    (net (code "125") (name "Y_S0") (class "Default")
      (node (ref "TEENSY++") (pin "C5") (pinfunction "15,PWM_C5") (pintype "bidirectional"))
      (node (ref "Y_MUX") (pin "10") (pinfunction "S0_10") (pintype "input"))
    )
    (net (code "126") (name "Y_S1") (class "Default")
      (node (ref "TEENSY++") (pin "C4") (pinfunction "14,PWM_C4") (pintype "bidirectional"))
      (node (ref "Y_MUX") (pin "11") (pinfunction "S1_11") (pintype "input"))
    )
    (net (code "127") (name "Y_S2") (class "Default")
      (node (ref "TEENSY++") (pin "C3") (pinfunction "13_C3") (pintype "bidirectional"))
      (node (ref "Y_MUX") (pin "14") (pinfunction "S2_14") (pintype "input"))
    )
    (net (code "128") (name "Y_S3") (class "Default")
      (node (ref "TEENSY++") (pin "C2") (pinfunction "12_C2") (pintype "bidirectional"))
      (node (ref "Y_MUX") (pin "13") (pinfunction "S3_13") (pintype "input"))
    )
    (net (code "129") (name "Y_SIG") (class "Default")
      (node (ref "TEENSY++") (pin "F3") (pinfunction "41,A3_F3") (pintype "bidirectional"))
      (node (ref "Y_MUX") (pin "1") (pinfunction "COM_1") (pintype "bidirectional"))
    )
    (net (code "130") (name "unconnected-(TEENSY++-0,PWM,INT0-PadD0)") (class "Default")
      (node (ref "TEENSY++") (pin "D0") (pinfunction "0,PWM,INT0_D0") (pintype "bidirectional"))
    )
    (net (code "131") (name "unconnected-(TEENSY++-1,PWM,INT1-PadD1)") (class "Default")
      (node (ref "TEENSY++") (pin "D1") (pinfunction "1,PWM,INT1_D1") (pintype "bidirectional"))
    )
    (net (code "132") (name "unconnected-(TEENSY++-2,RX,INT2-PadD2)") (class "Default")
      (node (ref "TEENSY++") (pin "D2") (pinfunction "2,RX,INT2_D2") (pintype "bidirectional"))
    )
    (net (code "133") (name "unconnected-(TEENSY++-3,TX,INT3-PadD3)") (class "Default")
      (node (ref "TEENSY++") (pin "D3") (pinfunction "3,TX,INT3_D3") (pintype "bidirectional"))
    )
    (net (code "134") (name "unconnected-(TEENSY++-16,PWM-PadC6)") (class "Default")
      (node (ref "TEENSY++") (pin "C6") (pinfunction "16,PWM_C6") (pintype "bidirectional"))
    )
    (net (code "135") (name "unconnected-(TEENSY++-17-PadC7)") (class "Default")
      (node (ref "TEENSY++") (pin "C7") (pinfunction "17_C7") (pintype "bidirectional"))
    )
    (net (code "136") (name "unconnected-(TEENSY++-18,INT6-PadE6)") (class "Default")
      (node (ref "TEENSY++") (pin "E6") (pinfunction "18,INT6_E6") (pintype "bidirectional"))
    )
    (net (code "137") (name "unconnected-(TEENSY++-19-PadE7)") (class "Default")
      (node (ref "TEENSY++") (pin "E7") (pinfunction "19_E7") (pintype "bidirectional"))
    )
    (net (code "138") (name "unconnected-(TEENSY++-24,PWM-PadB4)") (class "Default")
      (node (ref "TEENSY++") (pin "B4") (pinfunction "24,PWM_B4") (pintype "bidirectional"))
    )
    (net (code "139") (name "unconnected-(TEENSY++-25,PWM-PadB5)") (class "Default")
      (node (ref "TEENSY++") (pin "B5") (pinfunction "25,PWM_B5") (pintype "bidirectional"))
    )
    (net (code "140") (name "unconnected-(TEENSY++-26,PWM-PadB6)") (class "Default")
      (node (ref "TEENSY++") (pin "B6") (pinfunction "26,PWM_B6") (pintype "bidirectional"))
    )
    (net (code "141") (name "unconnected-(TEENSY++-27,PWM-PadB7)") (class "Default")
      (node (ref "TEENSY++") (pin "B7") (pinfunction "27,PWM_B7") (pintype "bidirectional"))
    )
    (net (code "142") (name "unconnected-(TEENSY++-32-PadA4)") (class "Default")
      (node (ref "TEENSY++") (pin "A4") (pinfunction "32_A4") (pintype "bidirectional"))
    )
    (net (code "143") (name "unconnected-(TEENSY++-33-PadA5)") (class "Default")
      (node (ref "TEENSY++") (pin "A5") (pinfunction "33_A5") (pintype "bidirectional"))
    )
    (net (code "144") (name "unconnected-(TEENSY++-34-PadA6)") (class "Default")
      (node (ref "TEENSY++") (pin "A6") (pinfunction "34_A6") (pintype "bidirectional"))
    )
    (net (code "145") (name "unconnected-(TEENSY++-35-PadA7)") (class "Default")
      (node (ref "TEENSY++") (pin "A7") (pinfunction "35_A7") (pintype "bidirectional"))
    )
    (net (code "146") (name "unconnected-(TEENSY++-36,INT4-PadE4)") (class "Default")
      (node (ref "TEENSY++") (pin "E4") (pinfunction "36,INT4_E4") (pintype "bidirectional"))
    )
    (net (code "147") (name "unconnected-(TEENSY++-37,INT5-PadE5)") (class "Default")
      (node (ref "TEENSY++") (pin "E5") (pinfunction "37,INT5_E5") (pintype "bidirectional"))
    )
    (net (code "148") (name "unconnected-(TEENSY++-38,A0-PadF0)") (class "Default")
      (node (ref "TEENSY++") (pin "F0") (pinfunction "38,A0_F0") (pintype "bidirectional"))
    )
    (net (code "149") (name "unconnected-(TEENSY++-39,A1-PadF1)") (class "Default")
      (node (ref "TEENSY++") (pin "F1") (pinfunction "39,A1_F1") (pintype "bidirectional"))
    )
    (net (code "150") (name "unconnected-(TEENSY++-40,A2-PadF2)") (class "Default")
      (node (ref "TEENSY++") (pin "F2") (pinfunction "40,A2_F2") (pintype "bidirectional"))
    )
    (net (code "151") (name "unconnected-(TEENSY++-43,A5-PadF5)") (class "Default")
      (node (ref "TEENSY++") (pin "F5") (pinfunction "43,A5_F5") (pintype "bidirectional"))
    )
    (net (code "152") (name "unconnected-(TEENSY++-44,A6-PadF6)") (class "Default")
      (node (ref "TEENSY++") (pin "F6") (pinfunction "44,A6_F6") (pintype "bidirectional"))
    )
    (net (code "153") (name "unconnected-(TEENSY++-45,A7-PadF7)") (class "Default")
      (node (ref "TEENSY++") (pin "F7") (pinfunction "45,A7_F7") (pintype "bidirectional"))
    )
    (net (code "154") (name "unconnected-(TEENSY++-AREF-PadREF)") (class "Default")
      (node (ref "TEENSY++") (pin "REF") (pinfunction "AREF_REF") (pintype "input"))
    )
    (net (code "155") (name "unconnected-(TEENSY++-Pad+5V)") (class "Default")
      (node (ref "TEENSY++") (pin "+5V") (pinfunction "+5V_+5V") (pintype "power_in"))
    )
    (net (code "156") (name "unconnected-(TEENSY++-_RST-PadRST)") (class "Default")
      (node (ref "TEENSY++") (pin "RST") (pinfunction "_RST_RST") (pintype "input"))
    )
  )
)
